# Power.net
KiCad netlist of a schematic drawn in Altium Designer
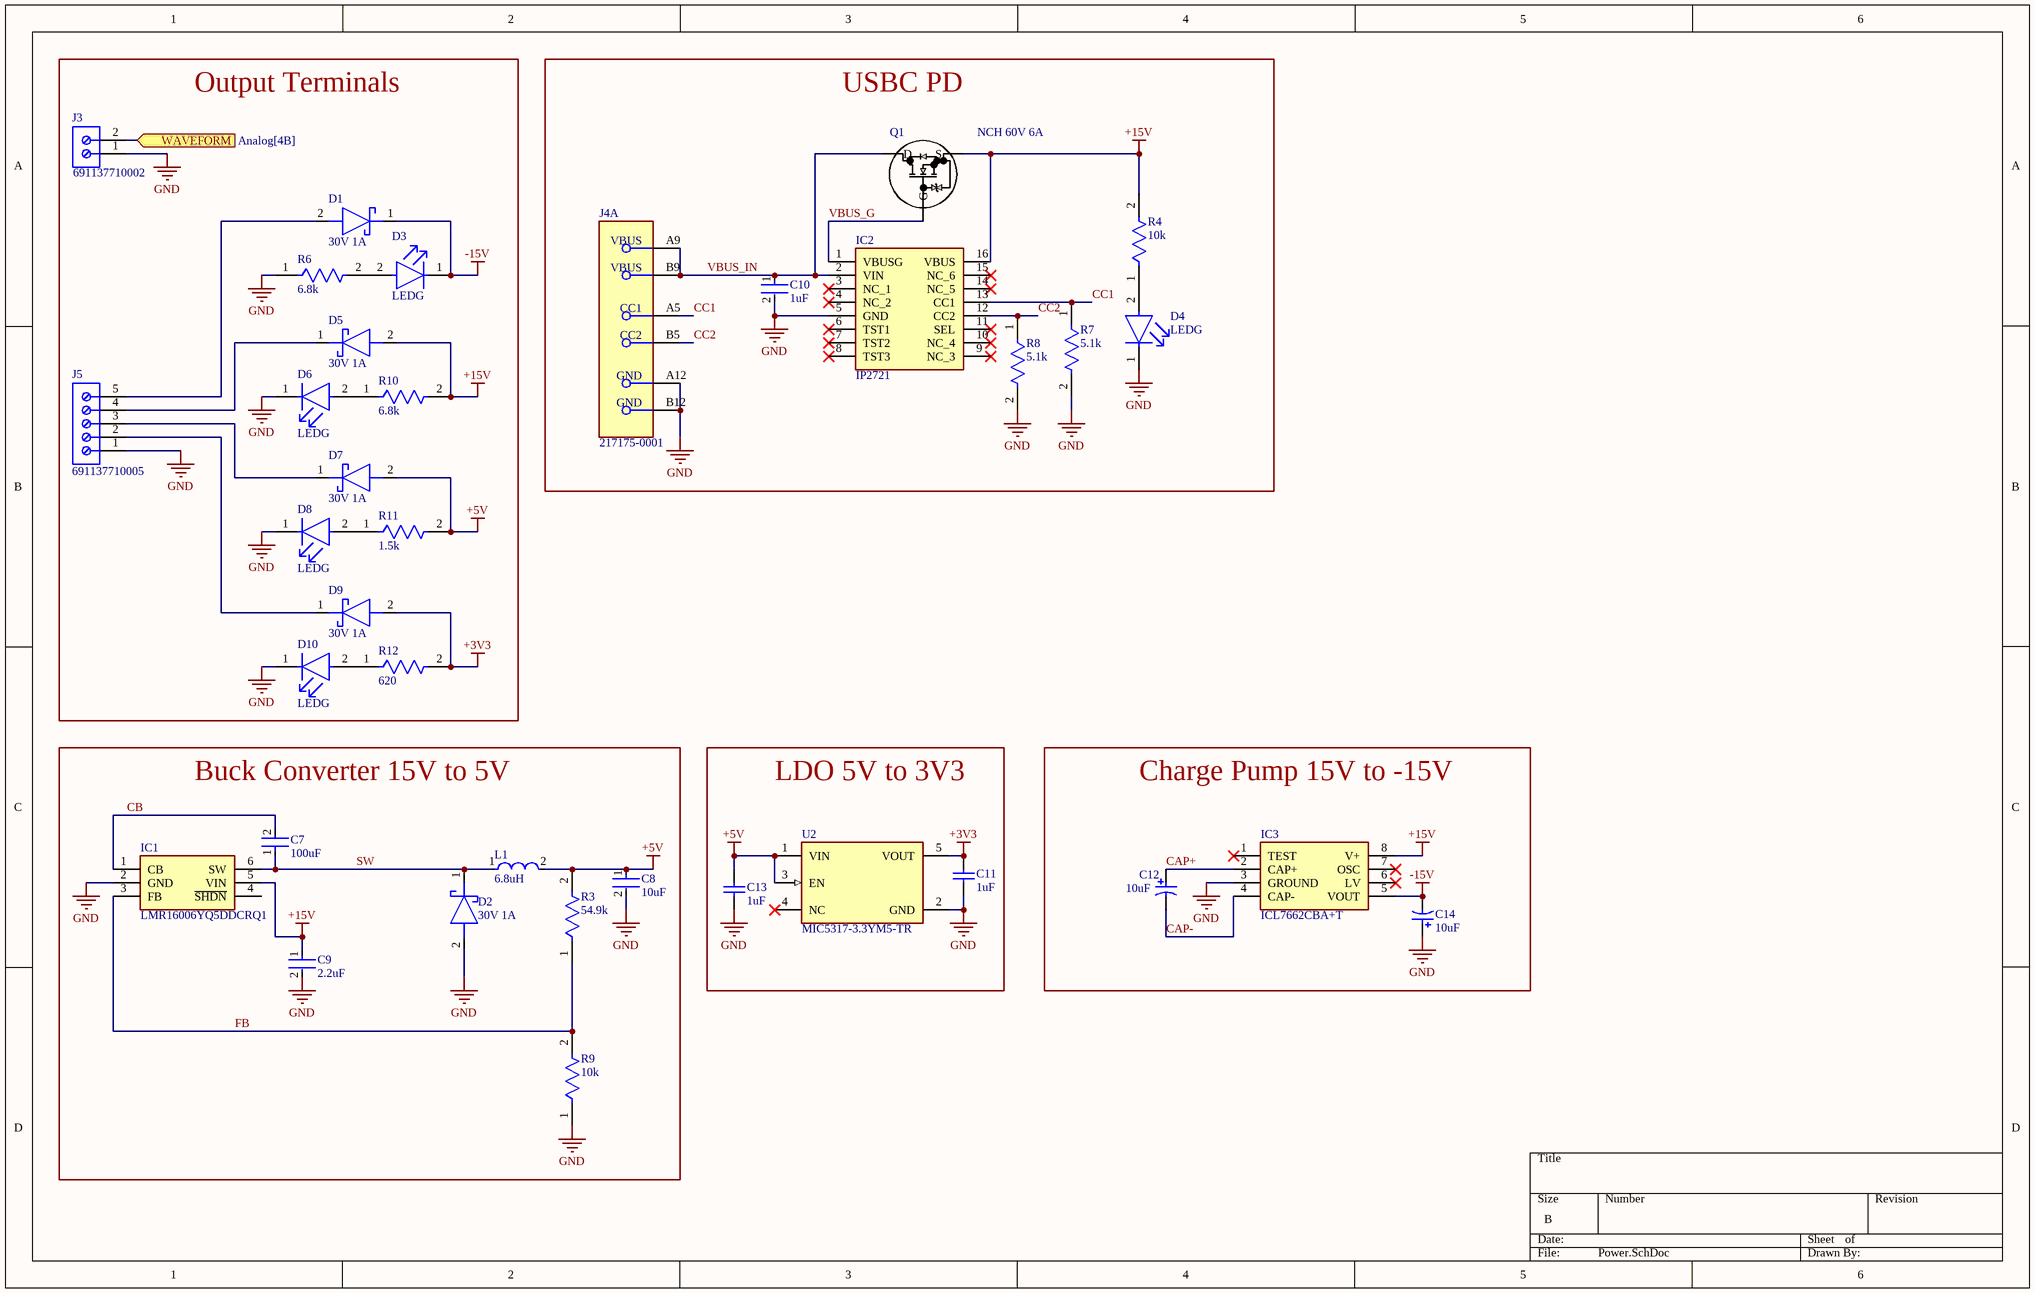
[diagram p0: Power.SchDoc]

(export (version "E")
  (design (tool "Eeschema 10.0.6"))
  (components
    (comp (ref "C7")
      (value "100uF")
      (footprint "FP-C1206C-EB-MFG")
      (description "C1206 0.10 μF C0G 10.00% 25 V X7R")
      (fields
        (field (name "TOLERANCE") "0.1")
        (field (name "OCTOPART") "https://octopart.com/c1206c104k3gactu-kemet-12901041")
      )
      (libsource (lib "Altium Content Vault") (part "b4654b650e69147ec39a6b967a45e02"))
    )
    (comp (ref "C8")
      (value "10uF")
      (footprint "FP-CL21-IPC_A")
      (description "CL21 Series 0805 10uF 25V ±10% Tolerance X5R Multilayer Ceramic Chip Capacitor")
      (fields (field (name "TOLERANCE") "10%"))
      (libsource (lib "Altium Content Vault") (part "b4654b650e69147ec39a6b967a45e02"))
    )
    (comp (ref "C9")
      (value "2.2uF")
      (footprint "FP-C0402-BB-MFG")
      (description "C0402 2,200 pF C0G 0.02 25 V")
      (fields
        (field (name "MANUFACTURER PART NUMBER") "C0402C222G3GACTU")
        (field (name "OCTOPART") "https://octopart.com/c0402c222g3gactu-kemet-87368565")
      )
      (libsource (lib "Altium Content Vault") (part "b4654b650e69147ec39a6b967a45e02"))
    )
    (comp (ref "C10")
      (value "1uF")
      (footprint "FP-CGA5L-0_3-0_1-IPC_B")
      (description "Cap Ceramic 1uF 25V X7R 20% Pad SMD 1206 +125°C Automotive T/R")
      (fields (field (name "TOLERANCE") "20%"))
      (libsource (lib "Altium Content Vault") (part "b4654b650e69147ec39a6b967a45e02"))
    )
    (comp (ref "C11")
      (value "1uF")
      (footprint "CAPC1206(3216)130_N")
      (description "CAP 1uF 10V ±5% 1206 (3216 Metric) Thickness 1.3mm SMD")
      (fields (field (name "TOLERANCE") "Â±5%"))
      (libsource (lib "Altium Content Vault") (part "CAP"))
    )
    (comp (ref "C12")
      (value "10uF")
      (footprint "VISH-293D-E_L")
      (fields (field (name "MANUFACTURER") "Vishay") (field (name "VOLTAGE") "50VDC"))
      (libsource (lib "Altium Content Vault") (part "CAP-P-2"))
    )
    (comp (ref "C13")
      (value "1uF")
      (footprint "CAPC1206(3216)130_N")
      (description "CAP 1uF 10V ±5% 1206 (3216 Metric) Thickness 1.3mm SMD")
      (fields (field (name "TOLERANCE") "Â±5%"))
      (libsource (lib "Altium Content Vault") (part "CAP"))
    )
    (comp (ref "C14")
      (value "10uF")
      (footprint "VISH-293D-E_L")
      (fields (field (name "MANUFACTURER") "Vishay") (field (name "VOLTAGE") "50VDC"))
      (libsource (lib "Altium Content Vault") (part "CAP-P-2"))
    )
    (comp (ref "D1")
      (value "30V 1A")
      (footprint "SamacSys:1SS357TPH3F")
      (description "Schottky Diode")
      (fields
        (field (name "MANUFACTURER_PART_NUMBER") "CUS10S30,H3F")
        (field (name "MOUSER PART NUMBER") "757-CUS10S30H3F")
      )
      (libsource (lib "*") (part "CUS10S30,H3F"))
    )
    (comp (ref "D2")
      (value "30V 1A")
      (footprint "SamacSys:1SS357TPH3F")
      (description "Schottky Diode")
      (fields
        (field (name "MANUFACTURER_PART_NUMBER") "CUS10S30,H3F")
        (field (name "MOUSER PART NUMBER") "757-CUS10S30H3F")
      )
      (libsource (lib "*") (part "CUS10S30,H3F"))
    )
    (comp (ref "D3")
      (value "LEDG")
      (footprint "FP-LTST-C170GKT-MFG")
      (description "LED GREEN CLEAR SMD")
      (fields (field (name "VOLTAGE") "5V"))
      (libsource (lib "Altium Content Vault") (part "8706943c75ba83719d021d2fdc84c58"))
    )
    (comp (ref "D4")
      (value "LEDG")
      (footprint "FP-LTST-C170GKT-MFG")
      (description "LED GREEN CLEAR SMD")
      (fields (field (name "VOLTAGE") "5V"))
      (libsource (lib "Altium Content Vault") (part "8706943c75ba83719d021d2fdc84c58"))
    )
    (comp (ref "D5")
      (value "30V 1A")
      (footprint "SamacSys:1SS357TPH3F")
      (description "Schottky Diode")
      (fields
        (field (name "MANUFACTURER_PART_NUMBER") "CUS10S30,H3F")
        (field (name "MOUSER PART NUMBER") "757-CUS10S30H3F")
      )
      (libsource (lib "*") (part "CUS10S30,H3F"))
    )
    (comp (ref "D6")
      (value "LEDG")
      (footprint "FP-LTST-C170GKT-MFG")
      (description "LED GREEN CLEAR SMD")
      (fields (field (name "VOLTAGE") "5V"))
      (libsource (lib "Altium Content Vault") (part "8706943c75ba83719d021d2fdc84c58"))
    )
    (comp (ref "D7")
      (value "30V 1A")
      (footprint "SamacSys:1SS357TPH3F")
      (description "Schottky Diode")
      (fields
        (field (name "MANUFACTURER_PART_NUMBER") "CUS10S30,H3F")
        (field (name "MOUSER PART NUMBER") "757-CUS10S30H3F")
      )
      (libsource (lib "*") (part "CUS10S30,H3F"))
    )
    (comp (ref "D8")
      (value "LEDG")
      (footprint "FP-LTST-C170GKT-MFG")
      (description "LED GREEN CLEAR SMD")
      (fields (field (name "VOLTAGE") "5V"))
      (libsource (lib "Altium Content Vault") (part "8706943c75ba83719d021d2fdc84c58"))
    )
    (comp (ref "D9")
      (value "30V 1A")
      (footprint "SamacSys:1SS357TPH3F")
      (description "Schottky Diode")
      (fields
        (field (name "MANUFACTURER_PART_NUMBER") "CUS10S30,H3F")
        (field (name "MOUSER PART NUMBER") "757-CUS10S30H3F")
      )
      (libsource (lib "*") (part "CUS10S30,H3F"))
    )
    (comp (ref "D10")
      (value "LEDG")
      (footprint "FP-LTST-C170GKT-MFG")
      (description "LED GREEN CLEAR SMD")
      (fields (field (name "VOLTAGE") "5V"))
      (libsource (lib "Altium Content Vault") (part "8706943c75ba83719d021d2fdc84c58"))
    )
    (comp (ref "IC1")
      (value "LMR16006YQ5DDCRQ1")
      (footprint "SamacSys:SOT95P280X110-6N")
      (description "Integrated Circuit")
      (fields (field (name "MOUSER PART NUMBER") "595-MR16006YQ5DDCRQ1"))
      (libsource (lib "*") (part "LMR16006YQ5DDCRQ1"))
    )
    (comp (ref "IC2")
      (value "IP2721")
      (footprint "SamacSys:SOP65P640X120-16N")
      (description "Integrated Circuit")
      (libsource (lib "*") (part "IP2721"))
    )
    (comp (ref "IC3")
      (value "ICL7662CBA+T")
      (footprint "SamacSys:SOIC127P600X175-8N")
      (description "Integrated Circuit")
      (fields (field (name "MOUSER PART NUMBER") "700-ICL7662CBAT"))
      (libsource (lib "*") (part "ICL7662CBA+T"))
    )
    (comp (ref "J3")
      (value "691137710002")
      (footprint "691137710002")
      (libsource (lib "Altium Content Vault") (part "TBL - 1R - 02P - Screw"))
    )
    (comp (ref "J4")
      (value "217175-0001")
      (footprint "FP-217175-0001-MFG")
      (description "CONN RCP USB2.0 C 6+18P SMD RA")
      (libsource (lib "Altium Content Vault") (part "6a66c69350f09309f94811689c98437"))
    )
    (comp (ref "J5")
      (value "691137710005")
      (footprint "691137710005")
      (libsource (lib "Altium Content Vault") (part "TBL - 1R - 05P - Screw"))
    )
    (comp (ref "L1")
      (value "6.8uH")
      (footprint "FP-LQH3NPH_ME-MFG")
      (description "Wire Wound Ferrite Inductor for Power Lines For Automotive 6.8μH ±20% 0.168Ω 1450mA 1212")
      (libsource (lib "Altium Content Vault") (part "725321dda6339637d4d059423bc1c3c"))
    )
    (comp (ref "Q1")
      (value "NCH 60V 6A")
      (footprint "SOT-323F_2-2U1S_UFM_TOS")
      (description "N-ch MOSFET, 60 V, 6.0 A, 0.036 Î©@10V, SOT-323F(UFM)")
      (fields
        (field (name "MANUFACTURER_PART_NUMBER") "SSM3K341TU,LF")
        (field (name "COPYRIGHT") "Copyright (C) 2025 Ultra Librarian. All rights reserved.")
      )
      (libsource (lib "Connectors") (part "SSM3K341TU,LF"))
    )
    (comp (ref "R3")
      (value "54.9k")
      (footprint "FP-TFCR0603-IPC_C")
      (description "RES Thin Film,  54.9kΩ, 0.25%, 0.1W, 50ppm/°C, 0603")
      (libsource (lib "Altium Content Vault") (part "1029c3af85768c4190bb7ad29bc67b5"))
    )
    (comp (ref "R4")
      (value "10k")
      (footprint "FP-AT0805-IPC_C")
      (description "Thin Film Chip Resistors Automotive Grade 10kΩ 0.1% 50ppm/°C 0805")
      (libsource (lib "Altium Content Vault") (part "1029c3af85768c4190bb7ad29bc67b5"))
    )
    (comp (ref "R6")
      (value "6.8k")
      (footprint "FP-RMCF0805-MFG")
      (description "6.8kΩ ±5% 0.125W 0805 Thick Film Chip Resistor AEC-Q200 compliant")
      (fields (field (name "TOLERANCE") "5%"))
      (libsource (lib "Altium Content Vault") (part "1029c3af85768c4190bb7ad29bc67b5"))
    )
    (comp (ref "R7")
      (value "5.1k")
      (footprint "FP-TFCR0603-IPC_A")
      (description "RES Thin Film,  5.1kΩ, 0.25%, 0.1W, 25ppm/°C, 0603")
      (libsource (lib "Altium Content Vault") (part "1029c3af85768c4190bb7ad29bc67b5"))
    )
    (comp (ref "R8")
      (value "5.1k")
      (footprint "FP-TFCR0603-IPC_A")
      (description "RES Thin Film,  5.1kΩ, 0.25%, 0.1W, 25ppm/°C, 0603")
      (libsource (lib "Altium Content Vault") (part "1029c3af85768c4190bb7ad29bc67b5"))
    )
    (comp (ref "R9")
      (value "10k")
      (footprint "FP-AT0805-IPC_C")
      (description "Thin Film Chip Resistors Automotive Grade 10kΩ 0.1% 50ppm/°C 0805")
      (libsource (lib "Altium Content Vault") (part "1029c3af85768c4190bb7ad29bc67b5"))
    )
    (comp (ref "R10")
      (value "6.8k")
      (footprint "FP-RMCF0805-MFG")
      (description "6.8kΩ ±5% 0.125W 0805 Thick Film Chip Resistor AEC-Q200 compliant")
      (fields (field (name "TOLERANCE") "5%"))
      (libsource (lib "Altium Content Vault") (part "1029c3af85768c4190bb7ad29bc67b5"))
    )
    (comp (ref "R11")
      (value "1.5k")
      (footprint "FP-TFCR0402-IPC_B")
      (description "RES Thin Film,  1.5kΩ, 1%, 0.063W, 100ppm/°C, 0402")
      (libsource (lib "Altium Content Vault") (part "1029c3af85768c4190bb7ad29bc67b5"))
    )
    (comp (ref "R12")
      (value "620")
      (footprint "FP-TFCR0603-IPC_B")
      (description "RES Thin Film,  620Ω, 0.25%, 0.1W, 25ppm/°C, 0603")
      (libsource (lib "Altium Content Vault") (part "1029c3af85768c4190bb7ad29bc67b5"))
    )
    (comp (ref "U2")
      (value "MIC5317-3.3YM5-TR")
      (footprint "FP-SOT23-5LD-PL-1-MFG")
      (description "IC REG LINEAR 3.3V 150MA SOT23-5")
      (libsource (lib "Altium Content Vault") (part "0a093dae7315cdc977fd108dde87457"))
    )
  )
  (nets
    (net (code "1") (name "+3V3") (class "Default")
      (node (ref "C11") (pin "2") (pinfunction "2_2") (pintype "passive"))
      (node (ref "D9") (pin "2") (pinfunction "A_2") (pintype "passive"))
      (node (ref "R12") (pin "2") (pinfunction "2_2") (pintype "passive"))
      (node (ref "U2") (pin "5") (pinfunction "VOUT_5") (pintype "power_in"))
    )
    (net (code "2") (name "+5V") (class "Default")
      (node (ref "C13") (pin "2") (pinfunction "2_2") (pintype "passive"))
      (node (ref "C8") (pin "1") (pinfunction "1_1") (pintype "passive"))
      (node (ref "D7") (pin "2") (pinfunction "A_2") (pintype "passive"))
      (node (ref "L1") (pin "2") (pinfunction "2_2") (pintype "passive"))
      (node (ref "R11") (pin "2") (pinfunction "2_2") (pintype "passive"))
      (node (ref "R3") (pin "2") (pinfunction "2_2") (pintype "passive"))
      (node (ref "U2") (pin "1") (pinfunction "VIN_1") (pintype "power_in"))
      (node (ref "U2") (pin "3") (pinfunction "EN_3") (pintype "input"))
    )
    (net (code "3") (name "+15V") (class "Default")
      (node (ref "C9") (pin "1") (pinfunction "1_1") (pintype "passive"))
      (node (ref "D5") (pin "2") (pinfunction "A_2") (pintype "passive"))
      (node (ref "IC1") (pin "5") (pinfunction "VIN_5") (pintype "passive"))
      (node (ref "IC2") (pin "16") (pinfunction "VBUS_16") (pintype "passive"))
      (node (ref "IC3") (pin "8") (pinfunction "V+_8") (pintype "passive"))
      (node (ref "Q1") (pin "2") (pinfunction "S_2") (pintype "passive"))
      (node (ref "R10") (pin "2") (pinfunction "2_2") (pintype "passive"))
      (node (ref "R4") (pin "2") (pinfunction "2_2") (pintype "passive"))
    )
    (net (code "4") (name "-15V") (class "Default")
      (node (ref "C14") (pin "2") (pinfunction "2_2") (pintype "passive"))
      (node (ref "D1") (pin "1") (pinfunction "K_1") (pintype "passive"))
      (node (ref "D3") (pin "1") (pinfunction "C_1") (pintype "passive"))
      (node (ref "IC3") (pin "5") (pinfunction "VOUT_5") (pintype "passive"))
    )
    (net (code "5") (name "/CAP+") (class "Default")
      (node (ref "C12") (pin "1") (pinfunction "1_1") (pintype "passive"))
      (node (ref "IC3") (pin "2") (pinfunction "CAP+_2") (pintype "passive"))
    )
    (net (code "6") (name "/CAP-") (class "Default")
      (node (ref "C12") (pin "2") (pinfunction "2_2") (pintype "passive"))
      (node (ref "IC3") (pin "4") (pinfunction "CAP-_4") (pintype "passive"))
    )
    (net (code "7") (name "/CB") (class "Default")
      (node (ref "C7") (pin "2") (pinfunction "2_2") (pintype "passive"))
      (node (ref "IC1") (pin "1") (pinfunction "CB_1") (pintype "passive"))
    )
    (net (code "8") (name "/CC1") (class "Default")
      (node (ref "IC2") (pin "13") (pinfunction "CC1_13") (pintype "passive"))
      (node (ref "J4") (pin "A5") (pinfunction "CC1_A5") (pintype "passive"))
      (node (ref "R7") (pin "1") (pinfunction "1_1") (pintype "passive"))
    )
    (net (code "9") (name "/CC2") (class "Default")
      (node (ref "IC2") (pin "12") (pinfunction "CC2_12") (pintype "passive"))
      (node (ref "J4") (pin "B5") (pinfunction "CC2_B5") (pintype "passive"))
      (node (ref "R8") (pin "1") (pinfunction "1_1") (pintype "passive"))
    )
    (net (code "10") (name "/FB") (class "Default")
      (node (ref "IC1") (pin "3") (pinfunction "FB_3") (pintype "passive"))
      (node (ref "R3") (pin "1") (pinfunction "1_1") (pintype "passive"))
      (node (ref "R9") (pin "2") (pinfunction "2_2") (pintype "passive"))
    )
    (net (code "11") (name "/SW") (class "Default")
      (node (ref "C7") (pin "1") (pinfunction "1_1") (pintype "passive"))
      (node (ref "D2") (pin "1") (pinfunction "K_1") (pintype "passive"))
      (node (ref "IC1") (pin "6") (pinfunction "SW_6") (pintype "passive"))
      (node (ref "L1") (pin "1") (pinfunction "1_1") (pintype "passive"))
    )
    (net (code "12") (name "/VBUS_G") (class "Default")
      (node (ref "IC2") (pin "1") (pinfunction "VBUSG_1") (pintype "passive"))
      (node (ref "Q1") (pin "1") (pinfunction "G_1") (pintype "passive"))
    )
    (net (code "13") (name "/VBUS_IN") (class "Default")
      (node (ref "C10") (pin "1") (pinfunction "1_1") (pintype "passive"))
      (node (ref "IC2") (pin "2") (pinfunction "VIN_2") (pintype "passive"))
      (node (ref "J4") (pin "A9") (pinfunction "VBUS_A9") (pintype "power_in"))
      (node (ref "J4") (pin "B9") (pinfunction "VBUS_B9") (pintype "power_in"))
      (node (ref "Q1") (pin "3") (pinfunction "D_3") (pintype "passive"))
    )
    (net (code "14") (name "/WAVEFORM") (class "Default")
      (node (ref "J3") (pin "2") (pinfunction "2_2") (pintype "passive"))
    )
    (net (code "15") (name "GND") (class "Default")
      (node (ref "C10") (pin "2") (pinfunction "2_2") (pintype "passive"))
      (node (ref "C11") (pin "1") (pinfunction "1_1") (pintype "passive"))
      (node (ref "C13") (pin "1") (pinfunction "1_1") (pintype "passive"))
      (node (ref "C14") (pin "1") (pinfunction "1_1") (pintype "passive"))
      (node (ref "C8") (pin "2") (pinfunction "2_2") (pintype "passive"))
      (node (ref "C9") (pin "2") (pinfunction "2_2") (pintype "passive"))
      (node (ref "D10") (pin "1") (pinfunction "C_1") (pintype "passive"))
      (node (ref "D2") (pin "2") (pinfunction "A_2") (pintype "passive"))
      (node (ref "D4") (pin "1") (pinfunction "C_1") (pintype "passive"))
      (node (ref "D6") (pin "1") (pinfunction "C_1") (pintype "passive"))
      (node (ref "D8") (pin "1") (pinfunction "C_1") (pintype "passive"))
      (node (ref "IC1") (pin "2") (pinfunction "GND_2") (pintype "passive"))
      (node (ref "IC2") (pin "5") (pinfunction "GND_5") (pintype "passive"))
      (node (ref "IC3") (pin "3") (pinfunction "GROUND_3") (pintype "passive"))
      (node (ref "J3") (pin "1") (pinfunction "1_1") (pintype "passive"))
      (node (ref "J4") (pin "A12") (pinfunction "GND_A12") (pintype "power_in"))
      (node (ref "J4") (pin "B12") (pinfunction "GND_B12") (pintype "power_in"))
      (node (ref "J5") (pin "1") (pinfunction "1_1") (pintype "passive"))
      (node (ref "R6") (pin "1") (pinfunction "1_1") (pintype "passive"))
      (node (ref "R7") (pin "2") (pinfunction "2_2") (pintype "passive"))
      (node (ref "R8") (pin "2") (pinfunction "2_2") (pintype "passive"))
      (node (ref "R9") (pin "1") (pinfunction "1_1") (pintype "passive"))
      (node (ref "U2") (pin "2") (pinfunction "GND_2") (pintype "power_in"))
    )
    (net (code "16") (name "Net-(D1-A)") (class "Default")
      (node (ref "D1") (pin "2") (pinfunction "A_2") (pintype "passive"))
      (node (ref "J5") (pin "5") (pinfunction "5_5") (pintype "passive"))
    )
    (net (code "17") (name "Net-(D3-A)") (class "Default")
      (node (ref "D3") (pin "2") (pinfunction "A_2") (pintype "passive"))
      (node (ref "R6") (pin "2") (pinfunction "2_2") (pintype "passive"))
    )
    (net (code "18") (name "Net-(D4-A)") (class "Default")
      (node (ref "D4") (pin "2") (pinfunction "A_2") (pintype "passive"))
      (node (ref "R4") (pin "1") (pinfunction "1_1") (pintype "passive"))
    )
    (net (code "19") (name "Net-(D5-K)") (class "Default")
      (node (ref "D5") (pin "1") (pinfunction "K_1") (pintype "passive"))
      (node (ref "J5") (pin "4") (pinfunction "4_4") (pintype "passive"))
    )
    (net (code "20") (name "Net-(D6-A)") (class "Default")
      (node (ref "D6") (pin "2") (pinfunction "A_2") (pintype "passive"))
      (node (ref "R10") (pin "1") (pinfunction "1_1") (pintype "passive"))
    )
    (net (code "21") (name "Net-(D7-K)") (class "Default")
      (node (ref "D7") (pin "1") (pinfunction "K_1") (pintype "passive"))
      (node (ref "J5") (pin "3") (pinfunction "3_3") (pintype "passive"))
    )
    (net (code "22") (name "Net-(D8-A)") (class "Default")
      (node (ref "D8") (pin "2") (pinfunction "A_2") (pintype "passive"))
      (node (ref "R11") (pin "1") (pinfunction "1_1") (pintype "passive"))
    )
    (net (code "23") (name "Net-(D9-K)") (class "Default")
      (node (ref "D9") (pin "1") (pinfunction "K_1") (pintype "passive"))
      (node (ref "J5") (pin "2") (pinfunction "2_2") (pintype "passive"))
    )
    (net (code "24") (name "Net-(D10-A)") (class "Default")
      (node (ref "D10") (pin "2") (pinfunction "A_2") (pintype "passive"))
      (node (ref "R12") (pin "1") (pinfunction "1_1") (pintype "passive"))
    )
    (net (code "25") (name "unconnected-(IC1-~{SHDN}-Pad4)") (class "Default")
      (node (ref "IC1") (pin "4") (pinfunction "~{SHDN}_4") (pintype "passive"))
    )
    (net (code "26") (name "unconnected-(IC2-NC_1-Pad3)") (class "Default")
      (node (ref "IC2") (pin "3") (pinfunction "NC_1_3") (pintype "passive+no_connect"))
    )
    (net (code "27") (name "unconnected-(IC2-NC_2-Pad4)") (class "Default")
      (node (ref "IC2") (pin "4") (pinfunction "NC_2_4") (pintype "passive+no_connect"))
    )
    (net (code "28") (name "unconnected-(IC2-NC_3-Pad9)") (class "Default")
      (node (ref "IC2") (pin "9") (pinfunction "NC_3_9") (pintype "passive+no_connect"))
    )
    (net (code "29") (name "unconnected-(IC2-NC_4-Pad10)") (class "Default")
      (node (ref "IC2") (pin "10") (pinfunction "NC_4_10") (pintype "passive+no_connect"))
    )
    (net (code "30") (name "unconnected-(IC2-NC_5-Pad14)") (class "Default")
      (node (ref "IC2") (pin "14") (pinfunction "NC_5_14") (pintype "passive+no_connect"))
    )
    (net (code "31") (name "unconnected-(IC2-NC_6-Pad15)") (class "Default")
      (node (ref "IC2") (pin "15") (pinfunction "NC_6_15") (pintype "passive+no_connect"))
    )
    (net (code "32") (name "unconnected-(IC2-SEL-Pad11)") (class "Default")
      (node (ref "IC2") (pin "11") (pinfunction "SEL_11") (pintype "passive+no_connect"))
    )
    (net (code "33") (name "unconnected-(IC2-TST1-Pad6)") (class "Default")
      (node (ref "IC2") (pin "6") (pinfunction "TST1_6") (pintype "passive+no_connect"))
    )
    (net (code "34") (name "unconnected-(IC2-TST2-Pad7)") (class "Default")
      (node (ref "IC2") (pin "7") (pinfunction "TST2_7") (pintype "passive+no_connect"))
    )
    (net (code "35") (name "unconnected-(IC2-TST3-Pad8)") (class "Default")
      (node (ref "IC2") (pin "8") (pinfunction "TST3_8") (pintype "passive+no_connect"))
    )
    (net (code "36") (name "unconnected-(IC3-LV-Pad6)") (class "Default")
      (node (ref "IC3") (pin "6") (pinfunction "LV_6") (pintype "passive+no_connect"))
    )
    (net (code "37") (name "unconnected-(IC3-OSC-Pad7)") (class "Default")
      (node (ref "IC3") (pin "7") (pinfunction "OSC_7") (pintype "passive+no_connect"))
    )
    (net (code "38") (name "unconnected-(IC3-TEST-Pad1)") (class "Default")
      (node (ref "IC3") (pin "1") (pinfunction "TEST_1") (pintype "passive+no_connect"))
    )
    (net (code "39") (name "unconnected-(U2-NC-Pad4)") (class "Default")
      (node (ref "U2") (pin "4") (pinfunction "NC_4") (pintype "passive+no_connect"))
    )
  )
)
